# main.net
KiCad netlist of a schematic drawn in Altium Designer
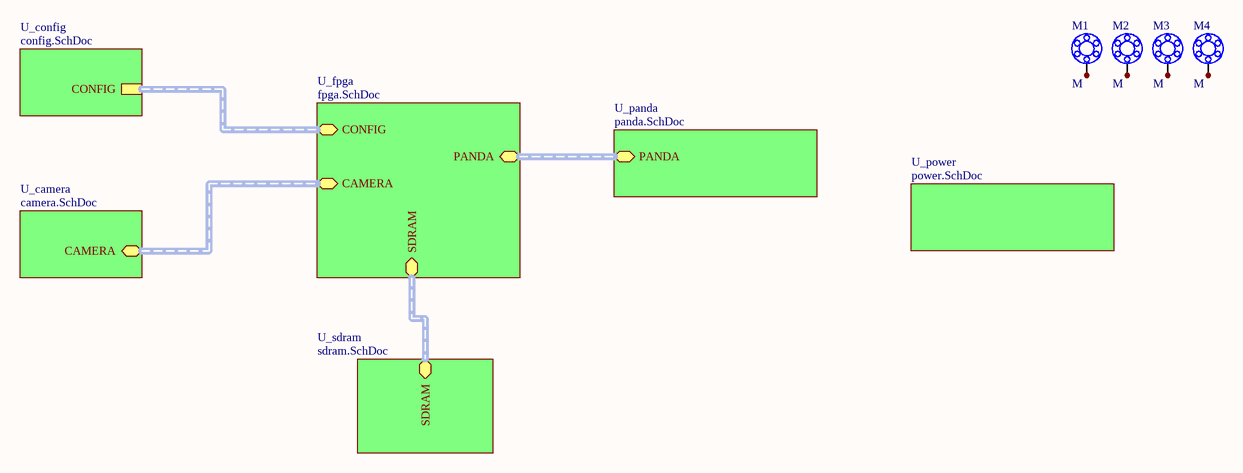
[diagram p0: main.SchDoc]

(export (version "E")
  (design (tool "Eeschema 10.0.6"))
  (components
    (comp (ref "M1")
      (value "M")
      (footprint "MOUNTING")
      (description "MOUNTING HOLE - NON INSTALLABLE")
      (libsource (lib "vh_Altium Library") (part "MOUNTING"))
    )
    (comp (ref "M2")
      (value "M")
      (footprint "MOUNTING")
      (description "MOUNTING HOLE - NON INSTALLABLE")
      (libsource (lib "vh_Altium Library") (part "MOUNTING"))
    )
    (comp (ref "M3")
      (value "M")
      (footprint "MOUNTING")
      (description "MOUNTING HOLE - NON INSTALLABLE")
      (libsource (lib "vh_Altium Library") (part "MOUNTING"))
    )
    (comp (ref "M4")
      (value "M")
      (footprint "MOUNTING")
      (description "MOUNTING HOLE - NON INSTALLABLE")
      (libsource (lib "vh_Altium Library") (part "MOUNTING"))
    )
  )
  (nets
    (net (code "5") (name "Net-(M1-Pad1)") (class "Default")
      (node (ref "M1") (pin "1") (pinfunction "1_1") (pintype "passive"))
      (node (ref "M1") (pin "2") (pinfunction "2_2") (pintype "passive"))
      (node (ref "M1") (pin "3") (pinfunction "3_3") (pintype "passive"))
      (node (ref "M1") (pin "4") (pinfunction "4_4") (pintype "passive"))
      (node (ref "M1") (pin "5") (pinfunction "5_5") (pintype "passive"))
      (node (ref "M1") (pin "6") (pinfunction "6_6") (pintype "passive"))
      (node (ref "M1") (pin "7") (pinfunction "7_7") (pintype "passive"))
    )
    (net (code "6") (name "Net-(M2-Pad1)") (class "Default")
      (node (ref "M2") (pin "1") (pinfunction "1_1") (pintype "passive"))
      (node (ref "M2") (pin "2") (pinfunction "2_2") (pintype "passive"))
      (node (ref "M2") (pin "3") (pinfunction "3_3") (pintype "passive"))
      (node (ref "M2") (pin "4") (pinfunction "4_4") (pintype "passive"))
      (node (ref "M2") (pin "5") (pinfunction "5_5") (pintype "passive"))
      (node (ref "M2") (pin "6") (pinfunction "6_6") (pintype "passive"))
      (node (ref "M2") (pin "7") (pinfunction "7_7") (pintype "passive"))
    )
    (net (code "7") (name "Net-(M3-Pad1)") (class "Default")
      (node (ref "M3") (pin "1") (pinfunction "1_1") (pintype "passive"))
      (node (ref "M3") (pin "2") (pinfunction "2_2") (pintype "passive"))
      (node (ref "M3") (pin "3") (pinfunction "3_3") (pintype "passive"))
      (node (ref "M3") (pin "4") (pinfunction "4_4") (pintype "passive"))
      (node (ref "M3") (pin "5") (pinfunction "5_5") (pintype "passive"))
      (node (ref "M3") (pin "6") (pinfunction "6_6") (pintype "passive"))
      (node (ref "M3") (pin "7") (pinfunction "7_7") (pintype "passive"))
    )
    (net (code "8") (name "Net-(M4-Pad1)") (class "Default")
      (node (ref "M4") (pin "1") (pinfunction "1_1") (pintype "passive"))
      (node (ref "M4") (pin "2") (pinfunction "2_2") (pintype "passive"))
      (node (ref "M4") (pin "3") (pinfunction "3_3") (pintype "passive"))
      (node (ref "M4") (pin "4") (pinfunction "4_4") (pintype "passive"))
      (node (ref "M4") (pin "5") (pinfunction "5_5") (pintype "passive"))
      (node (ref "M4") (pin "6") (pinfunction "6_6") (pintype "passive"))
      (node (ref "M4") (pin "7") (pinfunction "7_7") (pintype "passive"))
    )
  )
)
